# mcu.net
KiCad netlist of a schematic drawn in Altium Designer
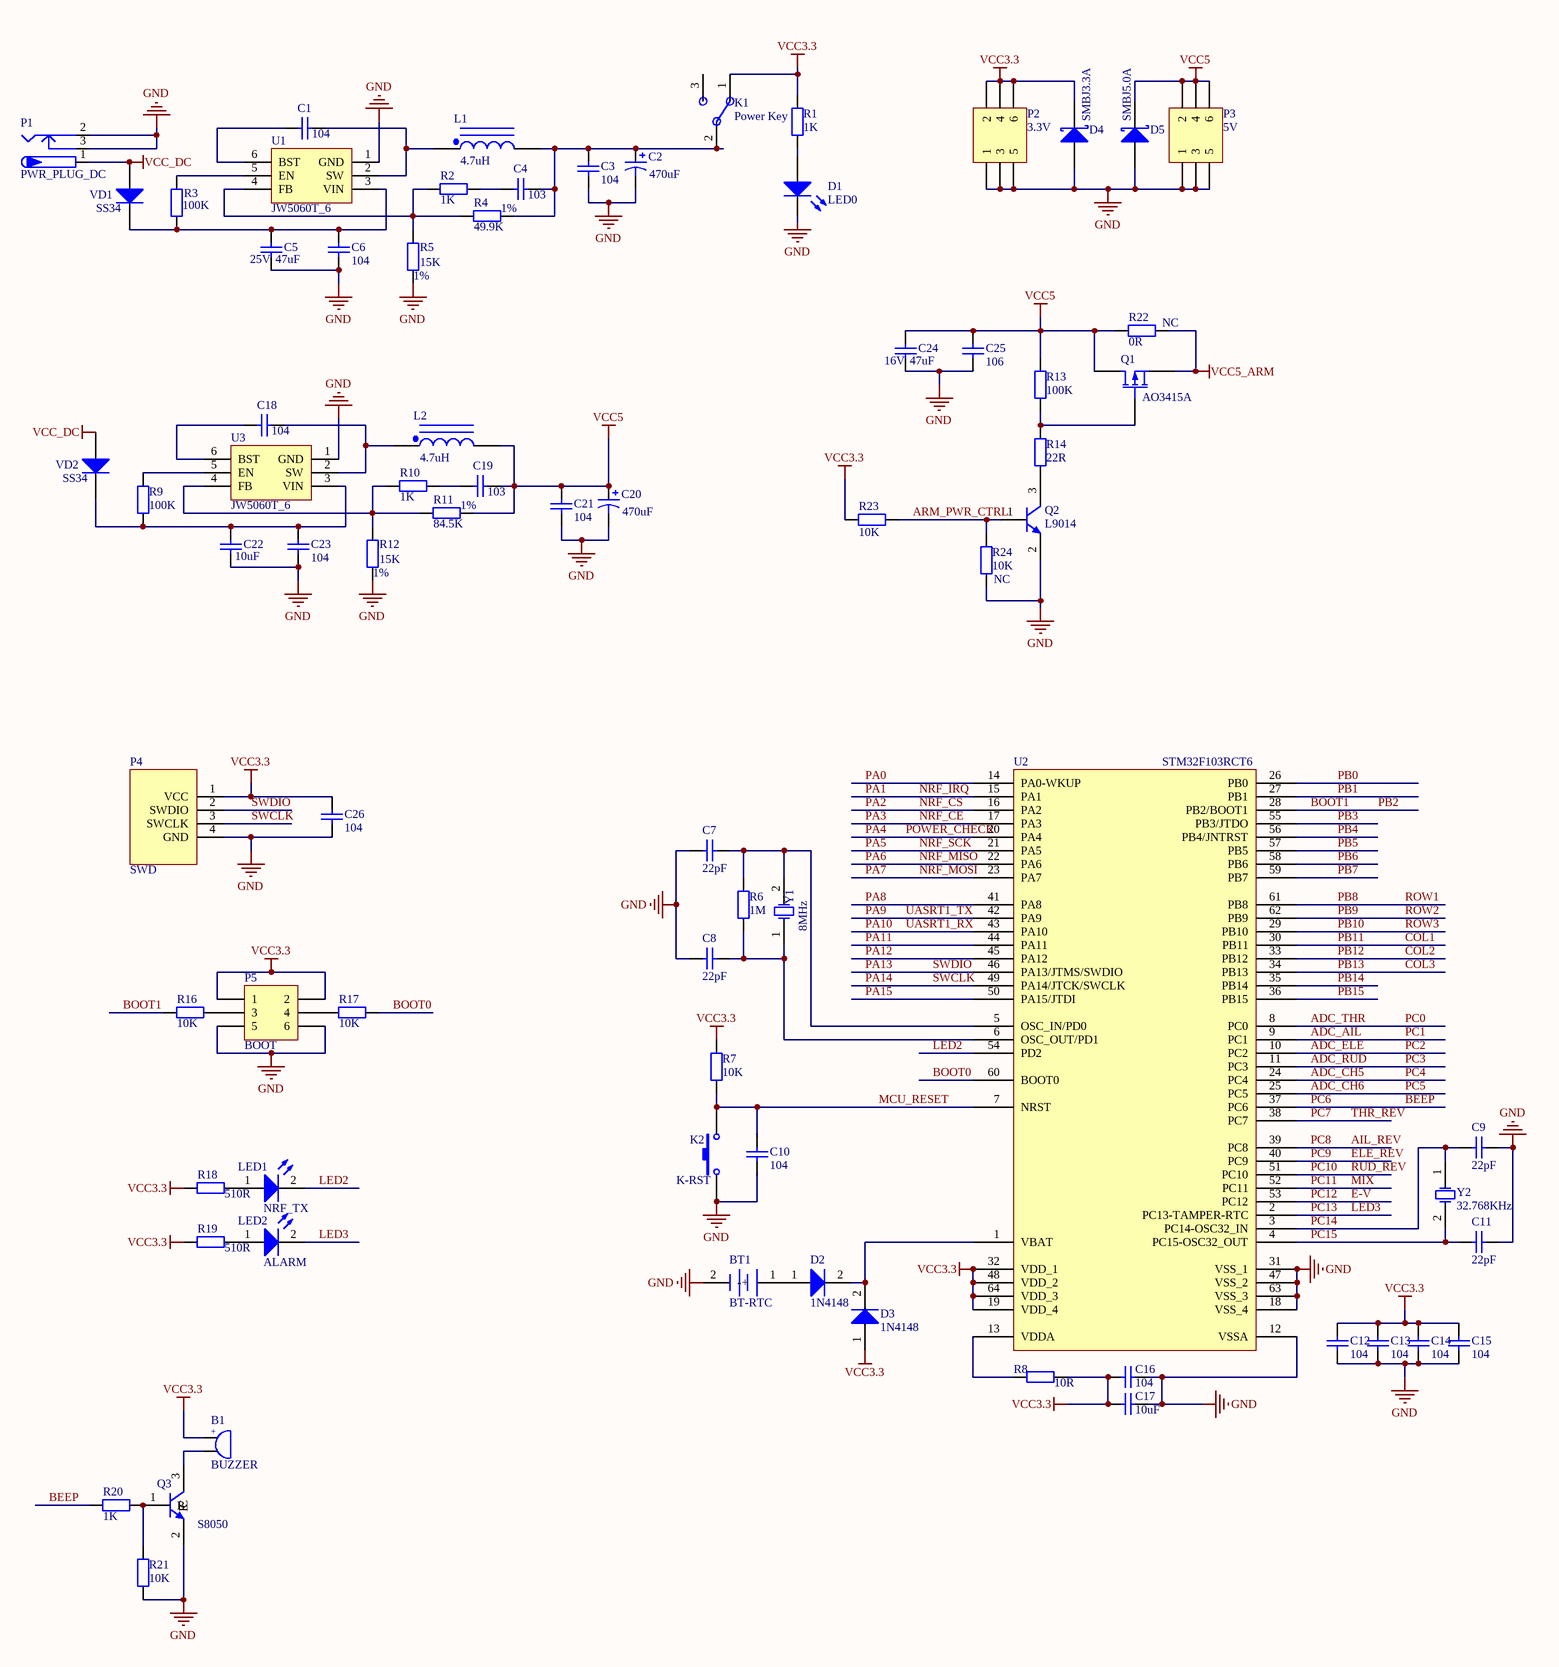
[diagram p0: mcu.SchDoc]

(export (version "E")
  (design (tool "Eeschema 10.0.6"))
  (components
    (comp (ref "B1")
      (value "BUZZER")
      (footprint "BEEP 5x9x5.5")
      (fields (field (name "版权归属") "源创客"))
      (libsource (lib "component") (part "BUZZER"))
    )
    (comp (ref "BT1")
      (value "BT-RTC")
      (footprint "BAT-RTC")
      (description "Multicell Battery")
      (fields (field (name "PUBLISHER") "Altium Limited"))
      (libsource (lib "Miscellaneous Devices") (part "Battery"))
    )
    (comp (ref "C1")
      (value "104")
      (footprint "RAD-0.3")
      (description "Capacitor")
      (fields (field (name "PUBLISHER") "Altium Limited"))
      (libsource (lib "Miscellaneous Devices") (part "Cap"))
    )
    (comp (ref "C2")
      (value "470uF")
      (footprint "RB7.6-15")
      (description "Polarized Capacitor (Radial)")
      (fields (field (name "Comment") "Cap Pol1") (field (name "PUBLISHER") "Altium Limited"))
      (libsource (lib "Miscellaneous Devices") (part "Cap Pol1"))
    )
    (comp (ref "C3")
      (value "104")
      (footprint "RAD-0.3")
      (description "Capacitor")
      (fields (field (name "PUBLISHER") "Altium Limited"))
      (libsource (lib "Miscellaneous Devices") (part "Cap"))
    )
    (comp (ref "C4")
      (value "103")
      (footprint "RAD-0.3")
      (description "Capacitor")
      (fields (field (name "PUBLISHER") "Altium Limited"))
      (libsource (lib "Miscellaneous Devices") (part "Cap"))
    )
    (comp (ref "C5")
      (value "25V")
      (footprint "RAD-0.3")
      (description "Capacitor")
      (fields (field (name "ALTIUM_VALUE") "47uF") (field (name "PUBLISHER") "Altium Limited"))
      (libsource (lib "Miscellaneous Devices") (part "Cap"))
    )
    (comp (ref "C6")
      (value "104")
      (footprint "RAD-0.3")
      (description "Capacitor")
      (fields (field (name "PUBLISHER") "Altium Limited"))
      (libsource (lib "Miscellaneous Devices") (part "Cap"))
    )
    (comp (ref "C7")
      (value "22pF")
      (footprint "0805")
      (description "Capacitor")
      (fields (field (name "Comment") "Cap") (field (name "PUBLISHER") "Altium Limited"))
      (libsource (lib "Miscellaneous Devices") (part "Cap"))
    )
    (comp (ref "C8")
      (value "22pF")
      (footprint "0805")
      (description "Capacitor")
      (fields (field (name "Comment") "Cap") (field (name "PUBLISHER") "Altium Limited"))
      (libsource (lib "Miscellaneous Devices") (part "Cap"))
    )
    (comp (ref "C9")
      (value "22pF")
      (footprint "0805")
      (description "Capacitor")
      (fields (field (name "Comment") "Cap") (field (name "PUBLISHER") "Altium Limited"))
      (libsource (lib "Miscellaneous Devices") (part "Cap"))
    )
    (comp (ref "C10")
      (value "104")
      (footprint "0805")
      (description "Capacitor")
      (fields (field (name "Comment") "Cap") (field (name "PUBLISHER") "Altium Limited"))
      (libsource (lib "Miscellaneous Devices") (part "Cap"))
    )
    (comp (ref "C11")
      (value "22pF")
      (footprint "0805")
      (description "Capacitor")
      (fields (field (name "Comment") "Cap") (field (name "PUBLISHER") "Altium Limited"))
      (libsource (lib "Miscellaneous Devices") (part "Cap"))
    )
    (comp (ref "C12")
      (value "104")
      (footprint "0805")
      (description "Capacitor")
      (fields (field (name "Comment") "Cap") (field (name "PUBLISHER") "Altium Limited"))
      (libsource (lib "Miscellaneous Devices") (part "Cap"))
    )
    (comp (ref "C13")
      (value "104")
      (footprint "0805")
      (description "Capacitor")
      (fields (field (name "Comment") "Cap") (field (name "PUBLISHER") "Altium Limited"))
      (libsource (lib "Miscellaneous Devices") (part "Cap"))
    )
    (comp (ref "C14")
      (value "104")
      (footprint "0805")
      (description "Capacitor")
      (fields (field (name "Comment") "Cap") (field (name "PUBLISHER") "Altium Limited"))
      (libsource (lib "Miscellaneous Devices") (part "Cap"))
    )
    (comp (ref "C15")
      (value "104")
      (footprint "0805")
      (description "Capacitor")
      (fields (field (name "Comment") "Cap") (field (name "PUBLISHER") "Altium Limited"))
      (libsource (lib "Miscellaneous Devices") (part "Cap"))
    )
    (comp (ref "C16")
      (value "104")
      (footprint "0805")
      (description "Capacitor")
      (fields (field (name "Comment") "Cap") (field (name "PUBLISHER") "Altium Limited"))
      (libsource (lib "Miscellaneous Devices") (part "Cap"))
    )
    (comp (ref "C17")
      (value "10uF")
      (footprint "0805")
      (description "Capacitor")
      (fields (field (name "Comment") "Cap") (field (name "PUBLISHER") "Altium Limited"))
      (libsource (lib "Miscellaneous Devices") (part "Cap"))
    )
    (comp (ref "C18")
      (value "104")
      (footprint "RAD-0.3")
      (description "Capacitor")
      (fields (field (name "PUBLISHER") "Altium Limited"))
      (libsource (lib "Miscellaneous Devices") (part "Cap"))
    )
    (comp (ref "C19")
      (value "103")
      (footprint "RAD-0.3")
      (description "Capacitor")
      (fields (field (name "PUBLISHER") "Altium Limited"))
      (libsource (lib "Miscellaneous Devices") (part "Cap"))
    )
    (comp (ref "C20")
      (value "470uF")
      (footprint "RB7.6-15")
      (description "Polarized Capacitor (Radial)")
      (fields (field (name "Comment") "Cap Pol1") (field (name "PUBLISHER") "Altium Limited"))
      (libsource (lib "Miscellaneous Devices") (part "Cap Pol1"))
    )
    (comp (ref "C21")
      (value "104")
      (footprint "RAD-0.3")
      (description "Capacitor")
      (fields (field (name "PUBLISHER") "Altium Limited"))
      (libsource (lib "Miscellaneous Devices") (part "Cap"))
    )
    (comp (ref "C22")
      (value "10uF")
      (footprint "RAD-0.3")
      (description "Capacitor")
      (fields (field (name "PUBLISHER") "Altium Limited"))
      (libsource (lib "Miscellaneous Devices") (part "Cap"))
    )
    (comp (ref "C23")
      (value "104")
      (footprint "RAD-0.3")
      (description "Capacitor")
      (fields (field (name "PUBLISHER") "Altium Limited"))
      (libsource (lib "Miscellaneous Devices") (part "Cap"))
    )
    (comp (ref "C24")
      (value "16V")
      (footprint "RAD-0.3")
      (description "Capacitor")
      (fields (field (name "ALTIUM_VALUE") "47uF") (field (name "PUBLISHER") "Altium Limited"))
      (libsource (lib "Miscellaneous Devices") (part "Cap"))
    )
    (comp (ref "C25")
      (value "106")
      (footprint "RAD-0.3")
      (description "Capacitor")
      (fields (field (name "PUBLISHER") "Altium Limited"))
      (libsource (lib "Miscellaneous Devices") (part "Cap"))
    )
    (comp (ref "C26")
      (value "104")
      (footprint "0805")
      (description "Capacitor")
      (fields (field (name "Comment") "Cap") (field (name "PUBLISHER") "Altium Limited"))
      (libsource (lib "Miscellaneous Devices") (part "Cap"))
    )
    (comp (ref "D1")
      (value "LED0")
      (footprint "LED-0")
      (description "Typical INFRARED GaAs LED")
      (fields (field (name "PUBLISHER") "Altium Limited"))
      (libsource (lib "") (part "LED0_1"))
    )
    (comp (ref "D2")
      (value "1N4148")
      (footprint "DIODE-1N4148")
      (description "Default Diode")
      (fields (field (name "PUBLISHER") "Altium Limited"))
      (libsource (lib "") (part "Diode_1"))
    )
    (comp (ref "D3")
      (value "1N4148")
      (footprint "DIODE-1N4148")
      (description "Default Diode")
      (fields (field (name "PUBLISHER") "Altium Limited"))
      (libsource (lib "") (part "Diode_1"))
    )
    (comp (ref "D4")
      (value "SMBJ3.3A")
      (footprint "TO-220AC")
      (description "Schottky Rectifier")
      (fields (field (name "PUBLISHER") "Altium Limited"))
      (libsource (lib "Miscellaneous Devices") (part "Diode 10TQ035"))
    )
    (comp (ref "D5")
      (value "SMBJ5.0A")
      (footprint "TO-220AC")
      (description "Schottky Rectifier")
      (fields (field (name "PUBLISHER") "Altium Limited"))
      (libsource (lib "Miscellaneous Devices") (part "Diode 10TQ035"))
    )
    (comp (ref "K1") (value "Power Key") (footprint "PKEY") (libsource (lib "component") (part "PWR_KEY")))
    (comp (ref "K2")
      (value "K-RST")
      (footprint "KEY")
      (description "Switch")
      (fields (field (name "PUBLISHER") "Altium Limited"))
      (libsource (lib "Miscellaneous Devices") (part "SW-PB"))
    )
    (comp (ref "L1")
      (value "4.7uH")
      (footprint "DIODE_SMC")
      (description "Magnetic-Core Inductor with Winding Polarity Marking")
      (fields (field (name "Comment") "Inductor Iron Dot") (field (name "PUBLISHER") "Altium Limited"))
      (libsource (lib "Miscellaneous Devices") (part "Inductor Iron Dot"))
    )
    (comp (ref "L2")
      (value "4.7uH")
      (footprint "DIODE_SMC")
      (description "Magnetic-Core Inductor with Winding Polarity Marking")
      (fields (field (name "Comment") "Inductor Iron Dot") (field (name "PUBLISHER") "Altium Limited"))
      (libsource (lib "Miscellaneous Devices") (part "Inductor Iron Dot"))
    )
    (comp (ref "LED1")
      (value "NRF_TX")
      (footprint "LED")
      (description "Typical INFRARED GaAs LED")
      (fields (field (name "PUBLISHER") "Altium Limited"))
      (libsource (lib "Miscellaneous Devices") (part "LED0"))
    )
    (comp (ref "LED2")
      (value "ALARM")
      (footprint "LED")
      (description "Typical INFRARED GaAs LED")
      (fields (field (name "PUBLISHER") "Altium Limited"))
      (libsource (lib "Miscellaneous Devices") (part "LED0"))
    )
    (comp (ref "P1")
      (value "PWR_PLUG_DC")
      (footprint "DC10B")
      (fields (field (name "版权归属") "源创客"))
      (libsource (lib "component") (part "PWR_PLUG_DC"))
    )
    (comp (ref "P2")
      (value "3.3V")
      (footprint "HDR2X3")
      (description "Header, 3-Pin, Dual row")
      (fields (field (name "PUBLISHER") "Altium Limited"))
      (libsource (lib "Miscellaneous Connectors") (part "Header 3X2"))
    )
    (comp (ref "P3")
      (value "5V")
      (footprint "HDR2X3")
      (description "Header, 3-Pin, Dual row")
      (fields (field (name "PUBLISHER") "Altium Limited"))
      (libsource (lib "Miscellaneous Connectors") (part "Header 3X2"))
    )
    (comp (ref "P4") (value "SWD") (libsource (lib "component") (part "SWD")))
    (comp (ref "P5")
      (value "BOOT")
      (footprint "HDR2X3")
      (description "Header, 3-Pin, Dual row")
      (fields (field (name "PUBLISHER") "Altium Limited"))
      (libsource (lib "") (part "Header 3X2_1"))
    )
    (comp (ref "Q1")
      (value "AO3415A")
      (footprint "E3")
      (description "P-Channel MOSFET")
      (fields (field (name "PUBLISHER") "Altium Limited"))
      (libsource (lib "Miscellaneous Devices") (part "MOSFET-P"))
    )
    (comp (ref "Q2") (value "L9014") (libsource (lib "component") (part "TRIODE_NPN")))
    (comp (ref "Q3") (value "S8050") (footprint "S8050") (libsource (lib "元件库") (part "S8050")))
    (comp (ref "R1")
      (value "1K")
      (footprint "AXIAL-0.4")
      (description "Resistor")
      (fields (field (name "PUBLISHER") "Altium Limited"))
      (libsource (lib "Miscellaneous Devices") (part "Res2"))
    )
    (comp (ref "R2")
      (value "1K")
      (footprint "AXIAL-0.4")
      (description "Resistor")
      (fields (field (name "PUBLISHER") "Altium Limited"))
      (libsource (lib "") (part "Res2_1"))
    )
    (comp (ref "R3")
      (value "100K")
      (footprint "AXIAL-0.4")
      (description "Resistor")
      (fields (field (name "PUBLISHER") "Altium Limited"))
      (libsource (lib "") (part "Res2_2"))
    )
    (comp (ref "R4")
      (value "1%")
      (footprint "AXIAL-0.4")
      (description "Resistor")
      (fields (field (name "ALTIUM_VALUE") "49.9K") (field (name "PUBLISHER") "Altium Limited"))
      (libsource (lib "") (part "Res2_1"))
    )
    (comp (ref "R5")
      (value "1%")
      (footprint "AXIAL-0.4")
      (description "Resistor")
      (fields (field (name "ALTIUM_VALUE") "15K") (field (name "PUBLISHER") "Altium Limited"))
      (libsource (lib "") (part "Res2_2"))
    )
    (comp (ref "R6")
      (value "1M")
      (footprint "0805")
      (description "Resistor")
      (fields (field (name "Comment") "Res2") (field (name "PUBLISHER") "Altium Limited"))
      (libsource (lib "Miscellaneous Devices") (part "Res2"))
    )
    (comp (ref "R7")
      (value "10K")
      (footprint "0805")
      (description "Resistor")
      (fields (field (name "Comment") "Res2") (field (name "PUBLISHER") "Altium Limited"))
      (libsource (lib "") (part "Res2_2"))
    )
    (comp (ref "R8")
      (value "10R")
      (footprint "0805")
      (description "Resistor")
      (fields (field (name "Comment") "Res2") (field (name "PUBLISHER") "Altium Limited"))
      (libsource (lib "") (part "Res2_1"))
    )
    (comp (ref "R9")
      (value "100K")
      (footprint "AXIAL-0.4")
      (description "Resistor")
      (fields (field (name "PUBLISHER") "Altium Limited"))
      (libsource (lib "Miscellaneous Devices") (part "Res2"))
    )
    (comp (ref "R10")
      (value "1K")
      (footprint "AXIAL-0.4")
      (description "Resistor")
      (fields (field (name "PUBLISHER") "Altium Limited"))
      (libsource (lib "") (part "Res2_1"))
    )
    (comp (ref "R11")
      (value "1%")
      (footprint "AXIAL-0.4")
      (description "Resistor")
      (fields (field (name "ALTIUM_VALUE") "84.5K") (field (name "PUBLISHER") "Altium Limited"))
      (libsource (lib "") (part "Res2_1"))
    )
    (comp (ref "R12")
      (value "1%")
      (footprint "AXIAL-0.4")
      (description "Resistor")
      (fields (field (name "ALTIUM_VALUE") "15K") (field (name "PUBLISHER") "Altium Limited"))
      (libsource (lib "") (part "Res2_2"))
    )
    (comp (ref "R13")
      (value "100K")
      (footprint "AXIAL-0.4")
      (description "Resistor")
      (fields (field (name "PUBLISHER") "Altium Limited"))
      (libsource (lib "Miscellaneous Devices") (part "Res2"))
    )
    (comp (ref "R14")
      (value "22R")
      (footprint "AXIAL-0.4")
      (description "Resistor")
      (fields (field (name "PUBLISHER") "Altium Limited"))
      (libsource (lib "Miscellaneous Devices") (part "Res2"))
    )
    (comp (ref "R16")
      (value "10K")
      (footprint "0805")
      (description "Resistor")
      (fields (field (name "Comment") "Res2") (field (name "PUBLISHER") "Altium Limited"))
      (libsource (lib "") (part "Res2_1"))
    )
    (comp (ref "R17")
      (value "10K")
      (footprint "0805")
      (description "Resistor")
      (fields (field (name "Comment") "Res2") (field (name "PUBLISHER") "Altium Limited"))
      (libsource (lib "") (part "Res2_1"))
    )
    (comp (ref "R18")
      (value "510R")
      (footprint "0805")
      (description "Resistor")
      (fields (field (name "Comment") "Res2") (field (name "PUBLISHER") "Altium Limited"))
      (libsource (lib "") (part "Res2_3"))
    )
    (comp (ref "R19")
      (value "510R")
      (footprint "0805")
      (description "Resistor")
      (fields (field (name "Comment") "Res2") (field (name "PUBLISHER") "Altium Limited"))
      (libsource (lib "") (part "Res2_3"))
    )
    (comp (ref "R20")
      (value "1K")
      (footprint "0805")
      (description "Resistor")
      (fields (field (name "Comment") "Res2") (field (name "PUBLISHER") "Altium Limited"))
      (libsource (lib "") (part "Res2_3"))
    )
    (comp (ref "R21")
      (value "10K")
      (footprint "0805")
      (description "Resistor")
      (fields (field (name "Comment") "Res2") (field (name "PUBLISHER") "Altium Limited"))
      (libsource (lib "") (part "Res2_2"))
    )
    (comp (ref "R22")
      (value "NC")
      (footprint "AXIAL-0.4")
      (description "Resistor")
      (fields (field (name "ALTIUM_VALUE") "0R") (field (name "PUBLISHER") "Altium Limited"))
      (libsource (lib "") (part "Res2_3"))
    )
    (comp (ref "R23")
      (value "10K")
      (footprint "AXIAL-0.4")
      (description "Resistor")
      (fields (field (name "PUBLISHER") "Altium Limited"))
      (libsource (lib "") (part "Res2_1"))
    )
    (comp (ref "R24")
      (value "NC")
      (footprint "AXIAL-0.4")
      (description "Resistor")
      (fields (field (name "ALTIUM_VALUE") "10K") (field (name "PUBLISHER") "Altium Limited"))
      (libsource (lib "Miscellaneous Devices") (part "Res2"))
    )
    (comp (ref "U1")
      (value "JW5060T_6")
      (description "电源稳压芯片，类似LDO。")
      (libsource (lib "component") (part "JW5060T_6"))
    )
    (comp (ref "U2")
      (value "STM32F103RCT6")
      (footprint "STM32F103RCT6")
      (libsource (lib "原理图库") (part "STM32F103RCT6"))
    )
    (comp (ref "U3")
      (value "JW5060T_6")
      (description "电源稳压芯片，类似LDO。")
      (libsource (lib "component") (part "JW5060T_6"))
    )
    (comp (ref "VD1")
      (value "SS34")
      (footprint "SMC")
      (description "Default Diode")
      (fields (field (name "PUBLISHER") "Altium Limited"))
      (libsource (lib "Miscellaneous Devices") (part "Diode"))
    )
    (comp (ref "VD2")
      (value "SS34")
      (footprint "SMC")
      (description "Default Diode")
      (fields (field (name "PUBLISHER") "Altium Limited"))
      (libsource (lib "Miscellaneous Devices") (part "Diode"))
    )
    (comp (ref "Y1")
      (value "8MHz")
      (footprint "CRYSTAL-8M")
      (description "Crystal Oscillator")
      (fields (field (name "PUBLISHER") "Altium Limited"))
      (libsource (lib "Miscellaneous Devices") (part "XTAL"))
    )
    (comp (ref "Y2")
      (value "32.768KHz")
      (footprint "CRYSTAL-RTC")
      (description "Crystal Oscillator")
      (fields (field (name "PUBLISHER") "Altium Limited"))
      (libsource (lib "Miscellaneous Devices") (part "XTAL"))
    )
  )
  (nets
    (net (code "1") (name "/ADC_AIL") (class "Default")
      (node (ref "U2") (pin "9") (pinfunction "PC1_9") (pintype "passive"))
    )
    (net (code "2") (name "/ADC_CH5") (class "Default")
      (node (ref "U2") (pin "24") (pinfunction "PC4_24") (pintype "passive"))
    )
    (net (code "3") (name "/ADC_CH6") (class "Default")
      (node (ref "U2") (pin "25") (pinfunction "PC5_25") (pintype "passive"))
    )
    (net (code "4") (name "/ADC_ELE") (class "Default")
      (node (ref "U2") (pin "10") (pinfunction "PC2_10") (pintype "passive"))
    )
    (net (code "5") (name "/ADC_RUD") (class "Default")
      (node (ref "U2") (pin "11") (pinfunction "PC3_11") (pintype "passive"))
    )
    (net (code "6") (name "/ADC_THR") (class "Default")
      (node (ref "U2") (pin "8") (pinfunction "PC0_8") (pintype "passive"))
    )
    (net (code "7") (name "/AIL_REV") (class "Default")
      (node (ref "U2") (pin "39") (pinfunction "PC8_39") (pintype "passive"))
    )
    (net (code "8") (name "/ARM_PWR_CTRL") (class "Default")
      (node (ref "Q2") (pin "1") (pinfunction "B_1") (pintype "passive"))
      (node (ref "R23") (pin "1") (pinfunction "1_1") (pintype "passive"))
      (node (ref "R24") (pin "1") (pinfunction "1_1") (pintype "passive"))
    )
    (net (code "9") (name "/BEEP") (class "Default")
      (node (ref "R20") (pin "1") (pinfunction "1_1") (pintype "passive"))
      (node (ref "U2") (pin "37") (pinfunction "PC6_37") (pintype "passive"))
    )
    (net (code "10") (name "/BOOT0") (class "Default")
      (node (ref "R17") (pin "1") (pinfunction "1_1") (pintype "passive"))
      (node (ref "U2") (pin "60") (pinfunction "BOOT0_60") (pintype "passive"))
    )
    (net (code "11") (name "/BOOT1") (class "Default")
      (node (ref "R16") (pin "2") (pinfunction "2_2") (pintype "passive"))
      (node (ref "U2") (pin "28") (pinfunction "PB2/BOOT1_28") (pintype "passive"))
    )
    (net (code "12") (name "/COL1") (class "Default")
      (node (ref "U2") (pin "30") (pinfunction "PB11_30") (pintype "passive"))
    )
    (net (code "13") (name "/COL2") (class "Default")
      (node (ref "U2") (pin "33") (pinfunction "PB12_33") (pintype "passive"))
    )
    (net (code "14") (name "/COL3") (class "Default")
      (node (ref "U2") (pin "34") (pinfunction "PB13_34") (pintype "passive"))
    )
    (net (code "15") (name "/E-V") (class "Default")
      (node (ref "U2") (pin "53") (pinfunction "PC12_53") (pintype "passive"))
    )
    (net (code "16") (name "/ELE_REV") (class "Default")
      (node (ref "U2") (pin "40") (pinfunction "PC9_40") (pintype "passive"))
    )
    (net (code "17") (name "/LED2") (class "Default")
      (node (ref "LED1") (pin "2") (pinfunction "K_2") (pintype "passive"))
      (node (ref "U2") (pin "54") (pinfunction "PD2_54") (pintype "passive"))
    )
    (net (code "18") (name "/LED3") (class "Default")
      (node (ref "LED2") (pin "2") (pinfunction "K_2") (pintype "passive"))
      (node (ref "U2") (pin "2") (pinfunction "PC13-TAMPER-RTC_2") (pintype "passive"))
    )
    (net (code "19") (name "/MCU_RESET") (class "Default")
      (node (ref "C10") (pin "2") (pinfunction "2_2") (pintype "passive"))
      (node (ref "K2") (pin "2") (pinfunction "2_2") (pintype "passive"))
      (node (ref "R7") (pin "1") (pinfunction "1_1") (pintype "passive"))
      (node (ref "U2") (pin "7") (pinfunction "NRST_7") (pintype "passive"))
    )
    (net (code "20") (name "/MIX") (class "Default")
      (node (ref "U2") (pin "52") (pinfunction "PC11_52") (pintype "passive"))
    )
    (net (code "21") (name "/NRF_CE") (class "Default")
      (node (ref "U2") (pin "17") (pinfunction "PA3_17") (pintype "passive"))
    )
    (net (code "22") (name "/NRF_CS") (class "Default")
      (node (ref "U2") (pin "16") (pinfunction "PA2_16") (pintype "passive"))
    )
    (net (code "23") (name "/NRF_IRQ") (class "Default")
      (node (ref "U2") (pin "15") (pinfunction "PA1_15") (pintype "passive"))
    )
    (net (code "24") (name "/NRF_MISO") (class "Default")
      (node (ref "U2") (pin "22") (pinfunction "PA6_22") (pintype "passive"))
    )
    (net (code "25") (name "/NRF_MOSI") (class "Default")
      (node (ref "U2") (pin "23") (pinfunction "PA7_23") (pintype "passive"))
    )
    (net (code "26") (name "/NRF_SCK") (class "Default")
      (node (ref "U2") (pin "21") (pinfunction "PA5_21") (pintype "passive"))
    )
    (net (code "27") (name "/PA0") (class "Default")
      (node (ref "U2") (pin "14") (pinfunction "PA0-WKUP_14") (pintype "passive"))
    )
    (net (code "28") (name "/PA4") (class "Default")
      (node (ref "U2") (pin "20") (pinfunction "PA4_20") (pintype "passive"))
    )
    (net (code "29") (name "/PA8") (class "Default")
      (node (ref "U2") (pin "41") (pinfunction "PA8_41") (pintype "passive"))
    )
    (net (code "30") (name "/PA9") (class "Default")
      (node (ref "U2") (pin "42") (pinfunction "PA9_42") (pintype "passive"))
    )
    (net (code "31") (name "/PA10") (class "Default")
      (node (ref "U2") (pin "43") (pinfunction "PA10_43") (pintype "passive"))
    )
    (net (code "32") (name "/PA11") (class "Default")
      (node (ref "U2") (pin "44") (pinfunction "PA11_44") (pintype "passive"))
    )
    (net (code "33") (name "/PA12") (class "Default")
      (node (ref "U2") (pin "45") (pinfunction "PA12_45") (pintype "passive"))
    )
    (net (code "34") (name "/PA13") (class "Default")
      (node (ref "P4") (pin "2") (pinfunction "SWDIO_2") (pintype "passive"))
      (node (ref "U2") (pin "46") (pinfunction "PA13/JTMS/SWDIO_46") (pintype "passive"))
    )
    (net (code "35") (name "/PA14") (class "Default")
      (node (ref "P4") (pin "3") (pinfunction "SWCLK_3") (pintype "passive"))
      (node (ref "U2") (pin "49") (pinfunction "PA14/JTCK/SWCLK_49") (pintype "passive"))
    )
    (net (code "36") (name "/PA15") (class "Default")
      (node (ref "U2") (pin "50") (pinfunction "PA15/JTDI_50") (pintype "passive"))
    )
    (net (code "37") (name "/PB0") (class "Default")
      (node (ref "U2") (pin "26") (pinfunction "PB0_26") (pintype "passive"))
    )
    (net (code "38") (name "/PB1") (class "Default")
      (node (ref "U2") (pin "27") (pinfunction "PB1_27") (pintype "passive"))
    )
    (net (code "39") (name "/PB3") (class "Default")
      (node (ref "U2") (pin "55") (pinfunction "PB3/JTDO_55") (pintype "passive"))
    )
    (net (code "40") (name "/PB4") (class "Default")
      (node (ref "U2") (pin "56") (pinfunction "PB4/JNTRST_56") (pintype "passive"))
    )
    (net (code "41") (name "/PB5") (class "Default")
      (node (ref "U2") (pin "57") (pinfunction "PB5_57") (pintype "passive"))
    )
    (net (code "42") (name "/PB6") (class "Default")
      (node (ref "U2") (pin "58") (pinfunction "PB6_58") (pintype "passive"))
    )
    (net (code "43") (name "/PB7") (class "Default")
      (node (ref "U2") (pin "59") (pinfunction "PB7_59") (pintype "passive"))
    )
    (net (code "44") (name "/PB8") (class "Default")
      (node (ref "U2") (pin "61") (pinfunction "PB8_61") (pintype "passive"))
    )
    (net (code "45") (name "/PB9") (class "Default")
      (node (ref "U2") (pin "62") (pinfunction "PB9_62") (pintype "passive"))
    )
    (net (code "46") (name "/PB10") (class "Default")
      (node (ref "U2") (pin "29") (pinfunction "PB10_29") (pintype "passive"))
    )
    (net (code "47") (name "/PB14") (class "Default")
      (node (ref "U2") (pin "35") (pinfunction "PB14_35") (pintype "passive"))
    )
    (net (code "48") (name "/PB15") (class "Default")
      (node (ref "U2") (pin "36") (pinfunction "PB15_36") (pintype "passive"))
    )
    (net (code "49") (name "/PC7") (class "Default")
      (node (ref "U2") (pin "38") (pinfunction "PC7_38") (pintype "passive"))
    )
    (net (code "50") (name "/PC10") (class "Default")
      (node (ref "U2") (pin "51") (pinfunction "PC10_51") (pintype "passive"))
    )
    (net (code "51") (name "/PC14") (class "Default")
      (node (ref "C9") (pin "1") (pinfunction "1_1") (pintype "passive"))
      (node (ref "U2") (pin "3") (pinfunction "PC14-OSC32_IN_3") (pintype "passive"))
      (node (ref "Y2") (pin "1") (pinfunction "OSC1_1") (pintype "passive"))
    )
    (net (code "52") (name "/PC15") (class "Default")
      (node (ref "C11") (pin "1") (pinfunction "1_1") (pintype "passive"))
      (node (ref "U2") (pin "4") (pinfunction "PC15-OSC32_OUT_4") (pintype "passive"))
      (node (ref "Y2") (pin "2") (pinfunction "OSC2_2") (pintype "passive"))
    )
    (net (code "53") (name "GND") (class "Default")
      (node (ref "BT1") (pin "2") (pinfunction "-_2") (pintype "passive"))
      (node (ref "C10") (pin "1") (pinfunction "1_1") (pintype "passive"))
      (node (ref "C11") (pin "2") (pinfunction "2_2") (pintype "passive"))
      (node (ref "C12") (pin "1") (pinfunction "1_1") (pintype "passive"))
      (node (ref "C13") (pin "1") (pinfunction "1_1") (pintype "passive"))
      (node (ref "C14") (pin "1") (pinfunction "1_1") (pintype "passive"))
      (node (ref "C15") (pin "1") (pinfunction "1_1") (pintype "passive"))
      (node (ref "C16") (pin "1") (pinfunction "1_1") (pintype "passive"))
      (node (ref "C17") (pin "1") (pinfunction "1_1") (pintype "passive"))
      (node (ref "C2") (pin "2") (pinfunction "2_2") (pintype "passive"))
      (node (ref "C20") (pin "2") (pinfunction "2_2") (pintype "passive"))
      (node (ref "C21") (pin "1") (pinfunction "1_1") (pintype "passive"))
      (node (ref "C22") (pin "1") (pinfunction "1_1") (pintype "passive"))
      (node (ref "C23") (pin "1") (pinfunction "1_1") (pintype "passive"))
      (node (ref "C24") (pin "1") (pinfunction "1_1") (pintype "passive"))
      (node (ref "C25") (pin "1") (pinfunction "1_1") (pintype "passive"))
      (node (ref "C26") (pin "1") (pinfunction "1_1") (pintype "passive"))
      (node (ref "C3") (pin "1") (pinfunction "1_1") (pintype "passive"))
      (node (ref "C5") (pin "1") (pinfunction "1_1") (pintype "passive"))
      (node (ref "C6") (pin "1") (pinfunction "1_1") (pintype "passive"))
      (node (ref "C7") (pin "2") (pinfunction "2_2") (pintype "passive"))
      (node (ref "C8") (pin "2") (pinfunction "2_2") (pintype "passive"))
      (node (ref "C9") (pin "2") (pinfunction "2_2") (pintype "passive"))
      (node (ref "D1") (pin "2") (pinfunction "K_2") (pintype "passive"))
      (node (ref "D4") (pin "3") (pinfunction "A_3") (pintype "passive"))
      (node (ref "D5") (pin "3") (pinfunction "A_3") (pintype "passive"))
      (node (ref "K2") (pin "1") (pinfunction "1_1") (pintype "passive"))
      (node (ref "P1") (pin "2") (pintype "power_in"))
      (node (ref "P1") (pin "3") (pintype "power_in"))
      (node (ref "P2") (pin "1") (pinfunction "1_1") (pintype "passive"))
      (node (ref "P2") (pin "3") (pinfunction "3_3") (pintype "passive"))
      (node (ref "P2") (pin "5") (pinfunction "5_5") (pintype "passive"))
      (node (ref "P3") (pin "1") (pinfunction "1_1") (pintype "passive"))
      (node (ref "P3") (pin "3") (pinfunction "3_3") (pintype "passive"))
      (node (ref "P3") (pin "5") (pinfunction "5_5") (pintype "passive"))
      (node (ref "P4") (pin "4") (pinfunction "GND_4") (pintype "passive"))
      (node (ref "P5") (pin "5") (pinfunction "5_5") (pintype "passive"))
      (node (ref "P5") (pin "6") (pinfunction "6_6") (pintype "passive"))
      (node (ref "Q2") (pin "2") (pinfunction "E_2") (pintype "passive"))
      (node (ref "Q3") (pin "2") (pinfunction "E_2") (pintype "passive"))
      (node (ref "R12") (pin "1") (pinfunction "1_1") (pintype "passive"))
      (node (ref "R21") (pin "1") (pinfunction "1_1") (pintype "passive"))
      (node (ref "R24") (pin "2") (pinfunction "2_2") (pintype "passive"))
      (node (ref "R5") (pin "1") (pinfunction "1_1") (pintype "passive"))
      (node (ref "U1") (pin "1") (pinfunction "GND_1") (pintype "passive"))
      (node (ref "U2") (pin "12") (pinfunction "VSSA_12") (pintype "passive"))
      (node (ref "U2") (pin "18") (pinfunction "VSS_4_18") (pintype "passive"))
      (node (ref "U2") (pin "31") (pinfunction "VSS_1_31") (pintype "passive"))
      (node (ref "U2") (pin "47") (pinfunction "VSS_2_47") (pintype "passive"))
      (node (ref "U2") (pin "63") (pinfunction "VSS_3_63") (pintype "passive"))
      (node (ref "U3") (pin "1") (pinfunction "GND_1") (pintype "passive"))
    )
    (net (code "54") (name "Net-(BT1-+)") (class "Default")
      (node (ref "BT1") (pin "1") (pinfunction "+_1") (pintype "passive"))
      (node (ref "D2") (pin "1") (pinfunction "A_1") (pintype "passive"))
    )
    (net (code "55") (name "Net-(C2-Pad1)") (class "Default")
      (node (ref "C2") (pin "1") (pinfunction "1_1") (pintype "passive"))
      (node (ref "C3") (pin "2") (pinfunction "2_2") (pintype "passive"))
      (node (ref "C4") (pin "2") (pinfunction "2_2") (pintype "passive"))
      (node (ref "K1") (pin "2") (pintype "passive"))
      (node (ref "L1") (pin "2") (pinfunction "2_2") (pintype "passive"))
      (node (ref "R4") (pin "1") (pinfunction "1_1") (pintype "passive"))
    )
    (net (code "56") (name "Net-(C4-Pad1)") (class "Default")
      (node (ref "C4") (pin "1") (pinfunction "1_1") (pintype "passive"))
      (node (ref "R2") (pin "1") (pinfunction "1_1") (pintype "passive"))
    )
    (net (code "57") (name "Net-(C19-Pad1)") (class "Default")
      (node (ref "C19") (pin "1") (pinfunction "1_1") (pintype "passive"))
      (node (ref "R10") (pin "1") (pinfunction "1_1") (pintype "passive"))
    )
    (net (code "58") (name "Net-(D1-A)") (class "Default")
      (node (ref "D1") (pin "1") (pinfunction "A_1") (pintype "passive"))
      (node (ref "R1") (pin "2") (pinfunction "2_2") (pintype "passive"))
    )
    (net (code "59") (name "Net-(D2-K)") (class "Default")
      (node (ref "D2") (pin "2") (pinfunction "K_2") (pintype "passive"))
      (node (ref "D3") (pin "2") (pinfunction "K_2") (pintype "passive"))
      (node (ref "U2") (pin "1") (pinfunction "VBAT_1") (pintype "passive"))
    )
    (net (code "60") (name "Net-(LED1-A)") (class "Default")
      (node (ref "LED1") (pin "1") (pinfunction "A_1") (pintype "passive"))
      (node (ref "R18") (pin "2") (pinfunction "2_2") (pintype "passive"))
    )
    (net (code "61") (name "Net-(LED2-A)") (class "Default")
      (node (ref "LED2") (pin "1") (pinfunction "A_1") (pintype "passive"))
      (node (ref "R19") (pin "2") (pinfunction "2_2") (pintype "passive"))
    )
    (net (code "62") (name "Net-(P5-Pad3)") (class "Default")
      (node (ref "P5") (pin "3") (pinfunction "3_3") (pintype "passive"))
      (node (ref "R16") (pin "1") (pinfunction "1_1") (pintype "passive"))
    )
    (net (code "63") (name "Net-(P5-Pad4)") (class "Default")
      (node (ref "P5") (pin "4") (pinfunction "4_4") (pintype "passive"))
      (node (ref "R17") (pin "2") (pinfunction "2_2") (pintype "passive"))
    )
    (net (code "64") (name "Net-(Q1-G)") (class "Default")
      (node (ref "Q1") (pin "2") (pinfunction "G_2") (pintype "passive"))
      (node (ref "R13") (pin "2") (pinfunction "2_2") (pintype "passive"))
      (node (ref "R14") (pin "1") (pinfunction "1_1") (pintype "passive"))
    )
    (net (code "65") (name "Net-(Q2-C)") (class "Default")
      (node (ref "Q2") (pin "3") (pinfunction "C_3") (pintype "passive"))
      (node (ref "R14") (pin "2") (pinfunction "2_2") (pintype "passive"))
    )
    (net (code "66") (name "Net-(Q3-B)") (class "Default")
      (node (ref "Q3") (pin "1") (pinfunction "B_1") (pintype "passive"))
      (node (ref "R20") (pin "2") (pinfunction "2_2") (pintype "passive"))
      (node (ref "R21") (pin "2") (pinfunction "2_2") (pintype "passive"))
    )
    (net (code "67") (name "Net-(Q3-C)") (class "Default")
      (node (ref "B1") (pin "2") (pinfunction "2_2") (pintype "passive"))
      (node (ref "Q3") (pin "3") (pinfunction "C_3") (pintype "passive"))
    )
    (net (code "68") (name "Net-(U1-BST)") (class "Default")
      (node (ref "C1") (pin "1") (pinfunction "1_1") (pintype "passive"))
      (node (ref "U1") (pin "6") (pinfunction "BST_6") (pintype "passive"))
    )
    (net (code "69") (name "Net-(U1-EN)") (class "Default")
      (node (ref "R3") (pin "2") (pinfunction "2_2") (pintype "passive"))
      (node (ref "U1") (pin "5") (pinfunction "EN_5") (pintype "passive"))
    )
    (net (code "70") (name "Net-(U1-FB)") (class "Default")
      (node (ref "R2") (pin "2") (pinfunction "2_2") (pintype "passive"))
      (node (ref "R4") (pin "2") (pinfunction "2_2") (pintype "passive"))
      (node (ref "R5") (pin "2") (pinfunction "2_2") (pintype "passive"))
      (node (ref "U1") (pin "4") (pinfunction "FB_4") (pintype "passive"))
    )
    (net (code "71") (name "Net-(U1-SW)") (class "Default")
      (node (ref "C1") (pin "2") (pinfunction "2_2") (pintype "passive"))
      (node (ref "L1") (pin "1") (pinfunction "1_1") (pintype "passive"))
      (node (ref "U1") (pin "2") (pinfunction "SW_2") (pintype "passive"))
    )
    (net (code "72") (name "Net-(U1-VIN)") (class "Default")
      (node (ref "C5") (pin "2") (pinfunction "2_2") (pintype "passive"))
      (node (ref "C6") (pin "2") (pinfunction "2_2") (pintype "passive"))
      (node (ref "R3") (pin "1") (pinfunction "1_1") (pintype "passive"))
      (node (ref "U1") (pin "3") (pinfunction "VIN_3") (pintype "passive"))
      (node (ref "VD1") (pin "2") (pinfunction "K_2") (pintype "passive"))
    )
    (net (code "73") (name "Net-(U2-OSC_IN{slash}PD0)") (class "Default")
      (node (ref "C7") (pin "1") (pinfunction "1_1") (pintype "passive"))
      (node (ref "R6") (pin "1") (pinfunction "1_1") (pintype "passive"))
      (node (ref "U2") (pin "5") (pinfunction "OSC_IN/PD0_5") (pintype "passive"))
      (node (ref "Y1") (pin "2") (pinfunction "OSC2_2") (pintype "passive"))
    )
    (net (code "74") (name "Net-(U2-OSC_OUT{slash}PD1)") (class "Default")
      (node (ref "C8") (pin "1") (pinfunction "1_1") (pintype "passive"))
      (node (ref "R6") (pin "2") (pinfunction "2_2") (pintype "passive"))
      (node (ref "U2") (pin "6") (pinfunction "OSC_OUT/PD1_6") (pintype "passive"))
      (node (ref "Y1") (pin "1") (pinfunction "OSC1_1") (pintype "passive"))
    )
    (net (code "75") (name "Net-(U2-VDDA)") (class "Default")
      (node (ref "R8") (pin "2") (pinfunction "2_2") (pintype "passive"))
      (node (ref "U2") (pin "13") (pinfunction "VDDA_13") (pintype "passive"))
    )
    (net (code "76") (name "Net-(U3-BST)") (class "Default")
      (node (ref "C18") (pin "1") (pinfunction "1_1") (pintype "passive"))
      (node (ref "U3") (pin "6") (pinfunction "BST_6") (pintype "passive"))
    )
    (net (code "77") (name "Net-(U3-EN)") (class "Default")
      (node (ref "R9") (pin "1") (pinfunction "1_1") (pintype "passive"))
      (node (ref "U3") (pin "5") (pinfunction "EN_5") (pintype "passive"))
    )
    (net (code "78") (name "Net-(U3-FB)") (class "Default")
      (node (ref "R10") (pin "2") (pinfunction "2_2") (pintype "passive"))
      (node (ref "R11") (pin "2") (pinfunction "2_2") (pintype "passive"))
      (node (ref "R12") (pin "2") (pinfunction "2_2") (pintype "passive"))
      (node (ref "U3") (pin "4") (pinfunction "FB_4") (pintype "passive"))
    )
    (net (code "79") (name "Net-(U3-SW)") (class "Default")
      (node (ref "C18") (pin "2") (pinfunction "2_2") (pintype "passive"))
      (node (ref "L2") (pin "1") (pinfunction "1_1") (pintype "passive"))
      (node (ref "U3") (pin "2") (pinfunction "SW_2") (pintype "passive"))
    )
    (net (code "80") (name "Net-(U3-VIN)") (class "Default")
      (node (ref "C22") (pin "2") (pinfunction "2_2") (pintype "passive"))
      (node (ref "C23") (pin "2") (pinfunction "2_2") (pintype "passive"))
      (node (ref "R9") (pin "2") (pinfunction "2_2") (pintype "passive"))
      (node (ref "U3") (pin "3") (pinfunction "VIN_3") (pintype "passive"))
      (node (ref "VD2") (pin "2") (pinfunction "K_2") (pintype "passive"))
    )
    (net (code "81") (name "VCC3.3") (class "Default")
      (node (ref "B1") (pin "1") (pinfunction "1_1") (pintype "passive"))
      (node (ref "C12") (pin "2") (pinfunction "2_2") (pintype "passive"))
      (node (ref "C13") (pin "2") (pinfunction "2_2") (pintype "passive"))
      (node (ref "C14") (pin "2") (pinfunction "2_2") (pintype "passive"))
      (node (ref "C15") (pin "2") (pinfunction "2_2") (pintype "passive"))
      (node (ref "C16") (pin "2") (pinfunction "2_2") (pintype "passive"))
      (node (ref "C17") (pin "2") (pinfunction "2_2") (pintype "passive"))
      (node (ref "C26") (pin "2") (pinfunction "2_2") (pintype "passive"))
      (node (ref "D3") (pin "1") (pinfunction "A_1") (pintype "passive"))
      (node (ref "D4") (pin "1") (pinfunction "K_1") (pintype "passive"))
      (node (ref "K1") (pin "1") (pintype "passive"))
      (node (ref "P2") (pin "2") (pinfunction "2_2") (pintype "passive"))
      (node (ref "P2") (pin "4") (pinfunction "4_4") (pintype "passive"))
      (node (ref "P2") (pin "6") (pinfunction "6_6") (pintype "passive"))
      (node (ref "P4") (pin "1") (pinfunction "VCC_1") (pintype "passive"))
      (node (ref "P5") (pin "1") (pinfunction "1_1") (pintype "passive"))
      (node (ref "P5") (pin "2") (pinfunction "2_2") (pintype "passive"))
      (node (ref "R1") (pin "1") (pinfunction "1_1") (pintype "passive"))
      (node (ref "R18") (pin "1") (pinfunction "1_1") (pintype "passive"))
      (node (ref "R19") (pin "1") (pinfunction "1_1") (pintype "passive"))
      (node (ref "R23") (pin "2") (pinfunction "2_2") (pintype "passive"))
      (node (ref "R7") (pin "2") (pinfunction "2_2") (pintype "passive"))
      (node (ref "R8") (pin "1") (pinfunction "1_1") (pintype "passive"))
      (node (ref "U2") (pin "19") (pinfunction "VDD_4_19") (pintype "passive"))
      (node (ref "U2") (pin "32") (pinfunction "VDD_1_32") (pintype "passive"))
      (node (ref "U2") (pin "48") (pinfunction "VDD_2_48") (pintype "passive"))
      (node (ref "U2") (pin "64") (pinfunction "VDD_3_64") (pintype "passive"))
    )
    (net (code "82") (name "VCC5") (class "Default")
      (node (ref "C19") (pin "2") (pinfunction "2_2") (pintype "passive"))
      (node (ref "C20") (pin "1") (pinfunction "1_1") (pintype "passive"))
      (node (ref "C21") (pin "2") (pinfunction "2_2") (pintype "passive"))
      (node (ref "C24") (pin "2") (pinfunction "2_2") (pintype "passive"))
      (node (ref "C25") (pin "2") (pinfunction "2_2") (pintype "passive"))
      (node (ref "D5") (pin "1") (pinfunction "K_1") (pintype "passive"))
      (node (ref "L2") (pin "2") (pinfunction "2_2") (pintype "passive"))
      (node (ref "P3") (pin "2") (pinfunction "2_2") (pintype "passive"))
      (node (ref "P3") (pin "4") (pinfunction "4_4") (pintype "passive"))
      (node (ref "P3") (pin "6") (pinfunction "6_6") (pintype "passive"))
      (node (ref "Q1") (pin "1") (pinfunction "D_1") (pintype "passive"))
      (node (ref "R11") (pin "1") (pinfunction "1_1") (pintype "passive"))
      (node (ref "R13") (pin "1") (pinfunction "1_1") (pintype "passive"))
      (node (ref "R22") (pin "1") (pinfunction "1_1") (pintype "passive"))
    )
    (net (code "83") (name "VCC5_ARM") (class "Default")
      (node (ref "Q1") (pin "3") (pinfunction "S_3") (pintype "passive"))
      (node (ref "R22") (pin "2") (pinfunction "2_2") (pintype "passive"))
    )
    (net (code "84") (name "VCC_DC") (class "Default")
      (node (ref "P1") (pin "1") (pintype "power_in"))
      (node (ref "VD1") (pin "1") (pinfunction "A_1") (pintype "passive"))
      (node (ref "VD2") (pin "1") (pinfunction "A_1") (pintype "passive"))
    )
    (net (code "85") (name "unconnected-(K1-Pad3)") (class "Default")
      (node (ref "K1") (pin "3") (pintype "passive"))
    )
  )
)
